# SCHE_balancing_robot_v2.net
KiCad netlist of a schematic drawn in Altium Designer
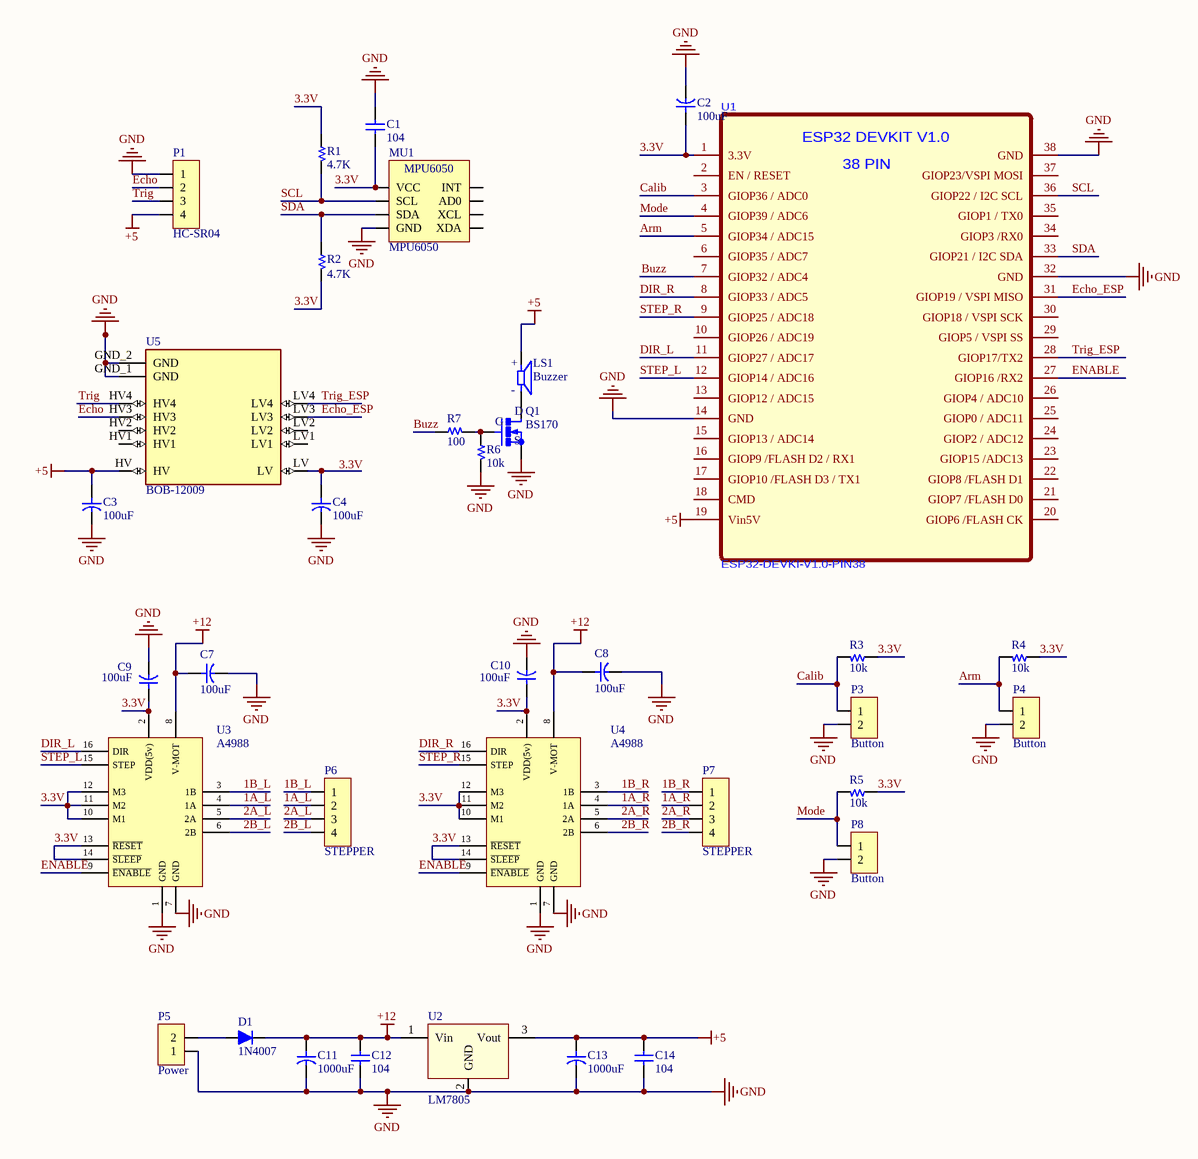
[diagram p0: SCHE_balancing_robot_v2.SchDoc]

(export (version "E")
  (design (tool "Eeschema 10.0.6"))
  (components
    (comp (ref "C1")
      (value "104")
      (footprint "CAP Ceramic/W300")
      (description "Capacitor non-pol")
      (libsource (lib "chipfc_libs") (part "Capacitor NP"))
    )
    (comp (ref "C2")
      (value "100uF")
      (footprint "CAP/D80/H125/LS35")
      (description "Capacitor pol")
      (libsource (lib "chipfc_libs") (part "Capacitor"))
    )
    (comp (ref "C3")
      (value "100uF")
      (footprint "CAP/D80/H125/LS35")
      (description "Capacitor pol")
      (libsource (lib "chipfc_libs") (part "Capacitor"))
    )
    (comp (ref "C4")
      (value "100uF")
      (footprint "CAP/D80/H125/LS35")
      (description "Capacitor pol")
      (libsource (lib "chipfc_libs") (part "Capacitor"))
    )
    (comp (ref "C7")
      (value "100uF")
      (footprint "CAP/D80/H125/LS35")
      (description "Capacitor pol")
      (libsource (lib "chipfc_libs") (part "Capacitor"))
    )
    (comp (ref "C8")
      (value "100uF")
      (footprint "CAP/D80/H125/LS35")
      (description "Capacitor pol")
      (libsource (lib "chipfc_libs") (part "Capacitor"))
    )
    (comp (ref "C9")
      (value "100uF")
      (footprint "CAP/D80/H125/LS35")
      (description "Capacitor pol")
      (libsource (lib "chipfc_libs") (part "Capacitor"))
    )
    (comp (ref "C10")
      (value "100uF")
      (footprint "CAP/D80/H125/LS35")
      (description "Capacitor pol")
      (libsource (lib "chipfc_libs") (part "Capacitor"))
    )
    (comp (ref "C11")
      (value "1000uF")
      (footprint "CYL/D.400/LS.200")
      (description "Capacitor pol")
      (libsource (lib "chipfc_libs") (part "Capacitor"))
    )
    (comp (ref "C12")
      (value "104")
      (footprint "CAP Ceramic/W300")
      (description "Capacitor non-pol")
      (libsource (lib "chipfc_libs") (part "Capacitor NP"))
    )
    (comp (ref "C13")
      (value "1000uF")
      (footprint "CYL/D.400/LS.200")
      (description "Capacitor pol")
      (libsource (lib "chipfc_libs") (part "Capacitor"))
    )
    (comp (ref "C14")
      (value "104")
      (footprint "CAP Ceramic/W300")
      (description "Capacitor non-pol")
      (libsource (lib "chipfc_libs") (part "Capacitor NP"))
    )
    (comp (ref "D1")
      (value "1N4007")
      (footprint "DO-41")
      (description "Default Diode")
      (libsource (lib "chipfc_libs") (part "Diode"))
    )
    (comp (ref "LS1")
      (value "Buzzer")
      (footprint "Buzzer-12MM")
      (fields (field (name "MP") "CST-951AP"))
      (libsource (lib "My Library") (part "Buzzer"))
    )
    (comp (ref "MU1")
      (value "MPU6050")
      (footprint "MPU6050")
      (fields
        (field (name "MANUFACTURER") "Würth Elektronik eiSos GmbH")
        (field (name "PARTNO") "613004143121")
        (field (name "CREATED BY") "Karrer Zheng")
      )
      (libsource (lib "My Library") (part "MPU6050"))
    )
    (comp (ref "P1")
      (value "HC-SR04")
      (footprint "HDR/Header/4/BOX")
      (description "Header, 4-Pin")
      (libsource (lib "connectors") (part "Header 4"))
    )
    (comp (ref "P3")
      (value "Button")
      (footprint "HDR/Terminal/2/5mm")
      (description "Header, 2-Pin")
      (libsource (lib "connectors") (part "Header 2"))
    )
    (comp (ref "P4")
      (value "Button")
      (footprint "HDR/Terminal/2/5mm")
      (description "Header, 2-Pin")
      (libsource (lib "connectors") (part "Header 2"))
    )
    (comp (ref "P5")
      (value "Power")
      (footprint "HDR/Terminal/2/5mm")
      (description "Header, 2-Pin")
      (libsource (lib "") (part "Header 2_1"))
    )
    (comp (ref "P6")
      (value "STEPPER")
      (footprint "HDR/Header/4/BOX")
      (description "Header, 4-Pin")
      (libsource (lib "connectors") (part "Header 4"))
    )
    (comp (ref "P7")
      (value "STEPPER")
      (footprint "HDR/Header/4/BOX")
      (description "Header, 4-Pin")
      (libsource (lib "connectors") (part "Header 4"))
    )
    (comp (ref "P8")
      (value "Button")
      (footprint "HDR/Terminal/2/5mm")
      (description "Header, 2-Pin")
      (libsource (lib "connectors") (part "Header 2"))
    )
    (comp (ref "Q1")
      (value "BS170")
      (footprint "TO92")
      (description "Nì±„ë„ 60V 500mA(Ta) 830mW(Ta) ê´€í†µí™€ TO-92-3")
      (fields (field (name "MF") "onsemi"))
      (libsource (lib "BS170") (part "BS170"))
    )
    (comp (ref "R1")
      (value "4.7K")
      (footprint "R 1/4W/300")
      (description "Resistor")
      (libsource (lib "chipfc_libs") (part "Resistor"))
    )
    (comp (ref "R2")
      (value "4.7K")
      (footprint "R 1/4W/300")
      (description "Resistor")
      (libsource (lib "chipfc_libs") (part "Resistor"))
    )
    (comp (ref "R3")
      (value "10k")
      (footprint "R 1/4W/300")
      (description "Resistor")
      (libsource (lib "chipfc_libs") (part "Resistor"))
    )
    (comp (ref "R4")
      (value "10k")
      (footprint "R 1/4W/300")
      (description "Resistor")
      (libsource (lib "chipfc_libs") (part "Resistor"))
    )
    (comp (ref "R5")
      (value "10k")
      (footprint "R 1/4W/300")
      (description "Resistor")
      (libsource (lib "chipfc_libs") (part "Resistor"))
    )
    (comp (ref "R6")
      (value "10k")
      (footprint "R 1/4W/300")
      (description "Resistor")
      (libsource (lib "chipfc_libs") (part "Resistor"))
    )
    (comp (ref "R7")
      (value "100")
      (footprint "R 1/4W/300")
      (description "Resistor")
      (libsource (lib "chipfc_libs") (part "Resistor"))
    )
    (comp (ref "U1")
      (value "ESP32-DEVKI-V1.0-PIN38")
      (footprint "ESP32-DEVKIT-V1.0-38PIN")
      (libsource (lib "My Library") (part "ESP32-DEVKI-V1.0-PIN38"))
    )
    (comp (ref "U2")
      (value "LM7805")
      (footprint "TO-220")
      (description "LDO Fixed Voltage regulator")
      (libsource (lib "chipfc_libs") (part "78xx"))
    )
    (comp (ref "U3")
      (value "A4988")
      (footprint "A4988(driver)")
      (libsource (lib "My Library") (part "A4988"))
    )
    (comp (ref "U4")
      (value "A4988")
      (footprint "A4988(driver)")
      (libsource (lib "My Library") (part "A4988"))
    )
    (comp (ref "U5")
      (value "BOB-12009")
      (footprint "CONV_BOB-12009")
      (description "BSS138 - Logic-Level Translator Interface Evaluation Board")
      (fields (field (name "MF") "SparkFun"))
      (libsource (lib "BOB-12009") (part "BOB-12009"))
    )
  )
  (nets
    (net (code "1") (name "+5") (class "Default")
      (node (ref "C13") (pin "1") (pinfunction "1_1") (pintype "passive"))
      (node (ref "C14") (pin "1") (pinfunction "1_1") (pintype "passive"))
      (node (ref "C3") (pin "1") (pinfunction "1_1") (pintype "passive"))
      (node (ref "LS1") (pin "1") (pinfunction "P_1") (pintype "passive"))
      (node (ref "P1") (pin "4") (pinfunction "4_4") (pintype "passive"))
      (node (ref "U1") (pin "19") (pinfunction "Vin5V_19") (pintype "passive"))
      (node (ref "U2") (pin "3") (pinfunction "Vout_3") (pintype "passive"))
      (node (ref "U5") (pin "HV") (pinfunction "HV_HV") (pintype "bidirectional"))
    )
    (net (code "2") (name "+12") (class "Default")
      (node (ref "C11") (pin "1") (pinfunction "1_1") (pintype "passive"))
      (node (ref "C12") (pin "1") (pinfunction "1_1") (pintype "passive"))
      (node (ref "C7") (pin "1") (pinfunction "1_1") (pintype "passive"))
      (node (ref "C8") (pin "1") (pinfunction "1_1") (pintype "passive"))
      (node (ref "D1") (pin "2") (pinfunction "K_2") (pintype "passive"))
      (node (ref "U2") (pin "1") (pinfunction "Vin_1") (pintype "power_in"))
      (node (ref "U3") (pin "8") (pinfunction "V-MOT_8") (pintype "power_in"))
      (node (ref "U4") (pin "8") (pinfunction "V-MOT_8") (pintype "power_in"))
    )
    (net (code "3") (name "/1A_L") (class "Default")
      (node (ref "P6") (pin "2") (pinfunction "2_2") (pintype "passive"))
      (node (ref "U3") (pin "4") (pinfunction "1A_4") (pintype "power_in"))
    )
    (net (code "4") (name "/1A_R") (class "Default")
      (node (ref "P7") (pin "2") (pinfunction "2_2") (pintype "passive"))
      (node (ref "U4") (pin "4") (pinfunction "1A_4") (pintype "power_in"))
    )
    (net (code "5") (name "/1B_L") (class "Default")
      (node (ref "P6") (pin "1") (pinfunction "1_1") (pintype "passive"))
      (node (ref "U3") (pin "3") (pinfunction "1B_3") (pintype "power_in"))
    )
    (net (code "6") (name "/1B_R") (class "Default")
      (node (ref "P7") (pin "1") (pinfunction "1_1") (pintype "passive"))
      (node (ref "U4") (pin "3") (pinfunction "1B_3") (pintype "power_in"))
    )
    (net (code "7") (name "/2A_L") (class "Default")
      (node (ref "P6") (pin "3") (pinfunction "3_3") (pintype "passive"))
      (node (ref "U3") (pin "5") (pinfunction "2A_5") (pintype "power_in"))
    )
    (net (code "8") (name "/2A_R") (class "Default")
      (node (ref "P7") (pin "3") (pinfunction "3_3") (pintype "passive"))
      (node (ref "U4") (pin "5") (pinfunction "2A_5") (pintype "power_in"))
    )
    (net (code "9") (name "/2B_L") (class "Default")
      (node (ref "P6") (pin "4") (pinfunction "4_4") (pintype "passive"))
      (node (ref "U3") (pin "6") (pinfunction "2B_6") (pintype "power_in"))
    )
    (net (code "10") (name "/2B_R") (class "Default")
      (node (ref "P7") (pin "4") (pinfunction "4_4") (pintype "passive"))
      (node (ref "U4") (pin "6") (pinfunction "2B_6") (pintype "power_in"))
    )
    (net (code "11") (name "/3.3V") (class "Default")
      (node (ref "C1") (pin "2") (pinfunction "2_2") (pintype "passive"))
      (node (ref "C10") (pin "1") (pinfunction "1_1") (pintype "passive"))
      (node (ref "C2") (pin "1") (pinfunction "1_1") (pintype "passive"))
      (node (ref "C9") (pin "1") (pinfunction "1_1") (pintype "passive"))
      (node (ref "MU1") (pin "1") (pinfunction "VCC_1") (pintype "passive"))
      (node (ref "R1") (pin "1") (pinfunction "1_1") (pintype "passive"))
      (node (ref "R2") (pin "2") (pinfunction "2_2") (pintype "passive"))
      (node (ref "R3") (pin "1") (pinfunction "1_1") (pintype "passive"))
      (node (ref "R4") (pin "1") (pinfunction "1_1") (pintype "passive"))
      (node (ref "R5") (pin "1") (pinfunction "1_1") (pintype "passive"))
      (node (ref "U1") (pin "1") (pinfunction "3.3V_1") (pintype "passive"))
      (node (ref "U3") (pin "10") (pinfunction "M1_10") (pintype "power_in"))
      (node (ref "U3") (pin "11") (pinfunction "M2_11") (pintype "power_in"))
      (node (ref "U3") (pin "12") (pinfunction "M3_12") (pintype "power_in"))
      (node (ref "U3") (pin "13") (pinfunction "~{RESET}_13") (pintype "power_in"))
      (node (ref "U3") (pin "14") (pinfunction "~{SLEEP}_14") (pintype "power_in"))
      (node (ref "U3") (pin "2") (pinfunction "VDD(5v)_2") (pintype "power_in"))
      (node (ref "U4") (pin "10") (pinfunction "M1_10") (pintype "power_in"))
      (node (ref "U4") (pin "11") (pinfunction "M2_11") (pintype "power_in"))
      (node (ref "U4") (pin "12") (pinfunction "M3_12") (pintype "power_in"))
      (node (ref "U4") (pin "13") (pinfunction "~{RESET}_13") (pintype "power_in"))
      (node (ref "U4") (pin "14") (pinfunction "~{SLEEP}_14") (pintype "power_in"))
      (node (ref "U4") (pin "2") (pinfunction "VDD(5v)_2") (pintype "power_in"))
    )
    (net (code "12") (name "/Arm") (class "Default")
      (node (ref "P4") (pin "1") (pinfunction "1_1") (pintype "passive"))
      (node (ref "R4") (pin "2") (pinfunction "2_2") (pintype "passive"))
      (node (ref "U1") (pin "5") (pinfunction "GIOP34_/_ADC15_5") (pintype "passive"))
    )
    (net (code "13") (name "/Buzz") (class "Default")
      (node (ref "R7") (pin "1") (pinfunction "1_1") (pintype "passive"))
      (node (ref "U1") (pin "7") (pinfunction "GIOP32_/_ADC4_7") (pintype "passive"))
    )
    (net (code "14") (name "/Calib") (class "Default")
      (node (ref "P3") (pin "1") (pinfunction "1_1") (pintype "passive"))
      (node (ref "R3") (pin "2") (pinfunction "2_2") (pintype "passive"))
      (node (ref "U1") (pin "3") (pinfunction "GIOP36_/_ADC0_3") (pintype "passive"))
    )
    (net (code "15") (name "/DIR_L") (class "Default")
      (node (ref "U1") (pin "11") (pinfunction "GIOP27_/_ADC17_11") (pintype "passive"))
      (node (ref "U3") (pin "16") (pinfunction "DIR_16") (pintype "power_in"))
    )
    (net (code "16") (name "/DIR_R") (class "Default")
      (node (ref "U1") (pin "8") (pinfunction "GIOP33_/_ADC5_8") (pintype "passive"))
      (node (ref "U4") (pin "16") (pinfunction "DIR_16") (pintype "power_in"))
    )
    (net (code "17") (name "/ENABLE") (class "Default")
      (node (ref "U1") (pin "27") (pinfunction "GIOP16_/RX2_27") (pintype "passive"))
      (node (ref "U3") (pin "9") (pinfunction "~{ENABLE}_9") (pintype "power_in"))
      (node (ref "U4") (pin "9") (pinfunction "~{ENABLE}_9") (pintype "power_in"))
    )
    (net (code "18") (name "/Echo") (class "Default")
      (node (ref "P1") (pin "2") (pinfunction "2_2") (pintype "passive"))
      (node (ref "U5") (pin "HV3") (pinfunction "HV3_HV3") (pintype "bidirectional"))
    )
    (net (code "19") (name "/Echo_ESP") (class "Default")
      (node (ref "U1") (pin "31") (pinfunction "GIOP19_/_VSPI_MISO_31") (pintype "passive"))
      (node (ref "U5") (pin "LV3") (pinfunction "LV3_LV3") (pintype "bidirectional"))
    )
    (net (code "20") (name "/Mode") (class "Default")
      (node (ref "P8") (pin "1") (pinfunction "1_1") (pintype "passive"))
      (node (ref "R5") (pin "2") (pinfunction "2_2") (pintype "passive"))
      (node (ref "U1") (pin "4") (pinfunction "GIOP39_/_ADC6_4") (pintype "passive"))
    )
    (net (code "21") (name "/SCL") (class "Default")
      (node (ref "MU1") (pin "3") (pinfunction "SCL_3") (pintype "passive"))
      (node (ref "R1") (pin "2") (pinfunction "2_2") (pintype "passive"))
      (node (ref "U1") (pin "36") (pinfunction "GIOP22_/_I2C_SCL_36") (pintype "passive"))
    )
    (net (code "22") (name "/SDA") (class "Default")
      (node (ref "MU1") (pin "4") (pinfunction "SDA_4") (pintype "passive"))
      (node (ref "R2") (pin "1") (pinfunction "1_1") (pintype "passive"))
      (node (ref "U1") (pin "33") (pinfunction "GIOP21_/_I2C_SDA_33") (pintype "passive"))
    )
    (net (code "23") (name "/STEP_L") (class "Default")
      (node (ref "U1") (pin "12") (pinfunction "GIOP14_/_ADC16_12") (pintype "passive"))
      (node (ref "U3") (pin "15") (pinfunction "STEP_15") (pintype "power_in"))
    )
    (net (code "24") (name "/STEP_R") (class "Default")
      (node (ref "U1") (pin "9") (pinfunction "GIOP25_/_ADC18_9") (pintype "passive"))
      (node (ref "U4") (pin "15") (pinfunction "STEP_15") (pintype "power_in"))
    )
    (net (code "25") (name "/Trig") (class "Default")
      (node (ref "P1") (pin "3") (pinfunction "3_3") (pintype "passive"))
      (node (ref "U5") (pin "HV4") (pinfunction "HV4_HV4") (pintype "bidirectional"))
    )
    (net (code "26") (name "/Trig_ESP") (class "Default")
      (node (ref "U1") (pin "28") (pinfunction "GIOP17/TX2_28") (pintype "passive"))
      (node (ref "U5") (pin "LV4") (pinfunction "LV4_LV4") (pintype "bidirectional"))
    )
    (net (code "27") (name "GND") (class "Default")
      (node (ref "C1") (pin "1") (pinfunction "1_1") (pintype "passive"))
      (node (ref "C10") (pin "2") (pinfunction "2_2") (pintype "passive"))
      (node (ref "C11") (pin "2") (pinfunction "2_2") (pintype "passive"))
      (node (ref "C12") (pin "2") (pinfunction "2_2") (pintype "passive"))
      (node (ref "C13") (pin "2") (pinfunction "2_2") (pintype "passive"))
      (node (ref "C14") (pin "2") (pinfunction "2_2") (pintype "passive"))
      (node (ref "C2") (pin "2") (pinfunction "2_2") (pintype "passive"))
      (node (ref "C3") (pin "2") (pinfunction "2_2") (pintype "passive"))
      (node (ref "C4") (pin "2") (pinfunction "2_2") (pintype "passive"))
      (node (ref "C7") (pin "2") (pinfunction "2_2") (pintype "passive"))
      (node (ref "C8") (pin "2") (pinfunction "2_2") (pintype "passive"))
      (node (ref "C9") (pin "2") (pinfunction "2_2") (pintype "passive"))
      (node (ref "MU1") (pin "2") (pinfunction "GND_2") (pintype "passive"))
      (node (ref "P1") (pin "1") (pinfunction "1_1") (pintype "passive"))
      (node (ref "P3") (pin "2") (pinfunction "2_2") (pintype "passive"))
      (node (ref "P4") (pin "2") (pinfunction "2_2") (pintype "passive"))
      (node (ref "P5") (pin "1") (pinfunction "1_1") (pintype "passive"))
      (node (ref "P8") (pin "2") (pinfunction "2_2") (pintype "passive"))
      (node (ref "Q1") (pin "3") (pinfunction "S_3") (pintype "passive"))
      (node (ref "R6") (pin "2") (pinfunction "2_2") (pintype "passive"))
      (node (ref "U1") (pin "14") (pinfunction "GND_14") (pintype "passive"))
      (node (ref "U1") (pin "32") (pinfunction "GND_32") (pintype "passive"))
      (node (ref "U1") (pin "38") (pinfunction "GND_38") (pintype "passive"))
      (node (ref "U2") (pin "2") (pinfunction "GND_2") (pintype "passive"))
      (node (ref "U3") (pin "1") (pinfunction "GND_1") (pintype "power_in"))
      (node (ref "U3") (pin "7") (pinfunction "GND_7") (pintype "power_in"))
      (node (ref "U4") (pin "1") (pinfunction "GND_1") (pintype "power_in"))
      (node (ref "U4") (pin "7") (pinfunction "GND_7") (pintype "power_in"))
      (node (ref "U5") (pin "GND_1") (pinfunction "GND_GND_1") (pintype "power_in"))
      (node (ref "U5") (pin "GND_2") (pinfunction "GND_GND_2") (pintype "power_in"))
    )
    (net (code "28") (name "Net-(C4-Pad1)") (class "Default")
      (node (ref "C4") (pin "1") (pinfunction "1_1") (pintype "passive"))
      (node (ref "U5") (pin "LV") (pinfunction "LV_LV") (pintype "bidirectional"))
    )
    (net (code "29") (name "Net-(D1-A)") (class "Default")
      (node (ref "D1") (pin "1") (pinfunction "A_1") (pintype "passive"))
      (node (ref "P5") (pin "2") (pinfunction "2_2") (pintype "passive"))
    )
    (net (code "30") (name "Net-(LS1-M)") (class "Default")
      (node (ref "LS1") (pin "2") (pinfunction "M_2") (pintype "passive"))
      (node (ref "Q1") (pin "1") (pinfunction "D_1") (pintype "passive"))
    )
    (net (code "31") (name "Net-(Q1-G)") (class "Default")
      (node (ref "Q1") (pin "2") (pinfunction "G_2") (pintype "passive"))
      (node (ref "R6") (pin "1") (pinfunction "1_1") (pintype "passive"))
      (node (ref "R7") (pin "2") (pinfunction "2_2") (pintype "passive"))
    )
    (net (code "32") (name "unconnected-(MU1-AD0-Pad7)") (class "Default")
      (node (ref "MU1") (pin "7") (pinfunction "AD0_7") (pintype "passive"))
    )
    (net (code "33") (name "unconnected-(MU1-INT-Pad8)") (class "Default")
      (node (ref "MU1") (pin "8") (pinfunction "INT_8") (pintype "passive"))
    )
    (net (code "34") (name "unconnected-(MU1-XCL-Pad6)") (class "Default")
      (node (ref "MU1") (pin "6") (pinfunction "XCL_6") (pintype "passive"))
    )
    (net (code "35") (name "unconnected-(MU1-XDA-Pad5)") (class "Default")
      (node (ref "MU1") (pin "5") (pinfunction "XDA_5") (pintype "passive"))
    )
    (net (code "36") (name "unconnected-(U1-CMD-Pad18)") (class "Default")
      (node (ref "U1") (pin "18") (pinfunction "CMD_18") (pintype "passive"))
    )
    (net (code "37") (name "unconnected-(U1-EN_{slash}_RESET-Pad2)") (class "Default")
      (node (ref "U1") (pin "2") (pinfunction "EN_/_RESET_2") (pintype "passive"))
    )
    (net (code "38") (name "unconnected-(U1-GIOP0_{slash}_ADC11-Pad25)") (class "Default")
      (node (ref "U1") (pin "25") (pinfunction "GIOP0_/_ADC11_25") (pintype "passive"))
    )
    (net (code "39") (name "unconnected-(U1-GIOP1_{slash}_TX0-Pad35)") (class "Default")
      (node (ref "U1") (pin "35") (pinfunction "GIOP1_/_TX0_35") (pintype "passive"))
    )
    (net (code "40") (name "unconnected-(U1-GIOP2_{slash}_ADC12-Pad24)") (class "Default")
      (node (ref "U1") (pin "24") (pinfunction "GIOP2_/_ADC12_24") (pintype "passive"))
    )
    (net (code "41") (name "unconnected-(U1-GIOP3_{slash}RX0-Pad34)") (class "Default")
      (node (ref "U1") (pin "34") (pinfunction "GIOP3_/RX0_34") (pintype "passive"))
    )
    (net (code "42") (name "unconnected-(U1-GIOP4_{slash}_ADC10-Pad26)") (class "Default")
      (node (ref "U1") (pin "26") (pinfunction "GIOP4_/_ADC10_26") (pintype "passive"))
    )
    (net (code "43") (name "unconnected-(U1-GIOP5_{slash}_VSPI_SS-Pad29)") (class "Default")
      (node (ref "U1") (pin "29") (pinfunction "GIOP5_/_VSPI_SS_29") (pintype "passive"))
    )
    (net (code "44") (name "unconnected-(U1-GIOP6_{slash}FLASH_CK-Pad20)") (class "Default")
      (node (ref "U1") (pin "20") (pinfunction "GIOP6_/FLASH_CK_20") (pintype "passive"))
    )
    (net (code "45") (name "unconnected-(U1-GIOP7_{slash}FLASH_D0-Pad21)") (class "Default")
      (node (ref "U1") (pin "21") (pinfunction "GIOP7_/FLASH_D0_21") (pintype "passive"))
    )
    (net (code "46") (name "unconnected-(U1-GIOP8_{slash}FLASH_D1-Pad22)") (class "Default")
      (node (ref "U1") (pin "22") (pinfunction "GIOP8_/FLASH_D1_22") (pintype "passive"))
    )
    (net (code "47") (name "unconnected-(U1-GIOP9_{slash}FLASH_D2_{slash}_RX1-Pad16)") (class "Default")
      (node (ref "U1") (pin "16") (pinfunction "GIOP9_/FLASH_D2_/_RX1_16") (pintype "passive"))
    )
    (net (code "48") (name "unconnected-(U1-GIOP10_{slash}FLASH_D3_{slash}_TX1-Pad17)") (class "Default")
      (node (ref "U1") (pin "17") (pinfunction "GIOP10_/FLASH_D3_/_TX1_17") (pintype "passive"))
    )
    (net (code "49") (name "unconnected-(U1-GIOP12_{slash}_ADC15-Pad13)") (class "Default")
      (node (ref "U1") (pin "13") (pinfunction "GIOP12_/_ADC15_13") (pintype "passive"))
    )
    (net (code "50") (name "unconnected-(U1-GIOP13_{slash}_ADC14-Pad15)") (class "Default")
      (node (ref "U1") (pin "15") (pinfunction "GIOP13_/_ADC14_15") (pintype "passive"))
    )
    (net (code "51") (name "unconnected-(U1-GIOP15_{slash}ADC13-Pad23)") (class "Default")
      (node (ref "U1") (pin "23") (pinfunction "GIOP15_/ADC13_23") (pintype "passive"))
    )
    (net (code "52") (name "unconnected-(U1-GIOP18_{slash}_VSPI_SCK-Pad30)") (class "Default")
      (node (ref "U1") (pin "30") (pinfunction "GIOP18_/_VSPI_SCK_30") (pintype "passive"))
    )
    (net (code "53") (name "unconnected-(U1-GIOP23{slash}VSPI_MOSI-Pad37)") (class "Default")
      (node (ref "U1") (pin "37") (pinfunction "GIOP23/VSPI_MOSI_37") (pintype "passive"))
    )
    (net (code "54") (name "unconnected-(U1-GIOP26_{slash}_ADC19-Pad10)") (class "Default")
      (node (ref "U1") (pin "10") (pinfunction "GIOP26_/_ADC19_10") (pintype "passive"))
    )
    (net (code "55") (name "unconnected-(U1-GIOP35_{slash}_ADC7-Pad6)") (class "Default")
      (node (ref "U1") (pin "6") (pinfunction "GIOP35_/_ADC7_6") (pintype "passive"))
    )
    (net (code "56") (name "unconnected-(U5-PadHV1)") (class "Default")
      (node (ref "U5") (pin "HV1") (pinfunction "HV1_HV1") (pintype "bidirectional"))
    )
    (net (code "57") (name "unconnected-(U5-PadHV2)") (class "Default")
      (node (ref "U5") (pin "HV2") (pinfunction "HV2_HV2") (pintype "bidirectional"))
    )
    (net (code "58") (name "unconnected-(U5-PadLV1)") (class "Default")
      (node (ref "U5") (pin "LV1") (pinfunction "LV1_LV1") (pintype "bidirectional"))
    )
    (net (code "59") (name "unconnected-(U5-PadLV2)") (class "Default")
      (node (ref "U5") (pin "LV2") (pinfunction "LV2_LV2") (pintype "bidirectional"))
    )
  )
)
